# LedCubeControl.net
KiCad netlist of a schematic drawn in EAGLE
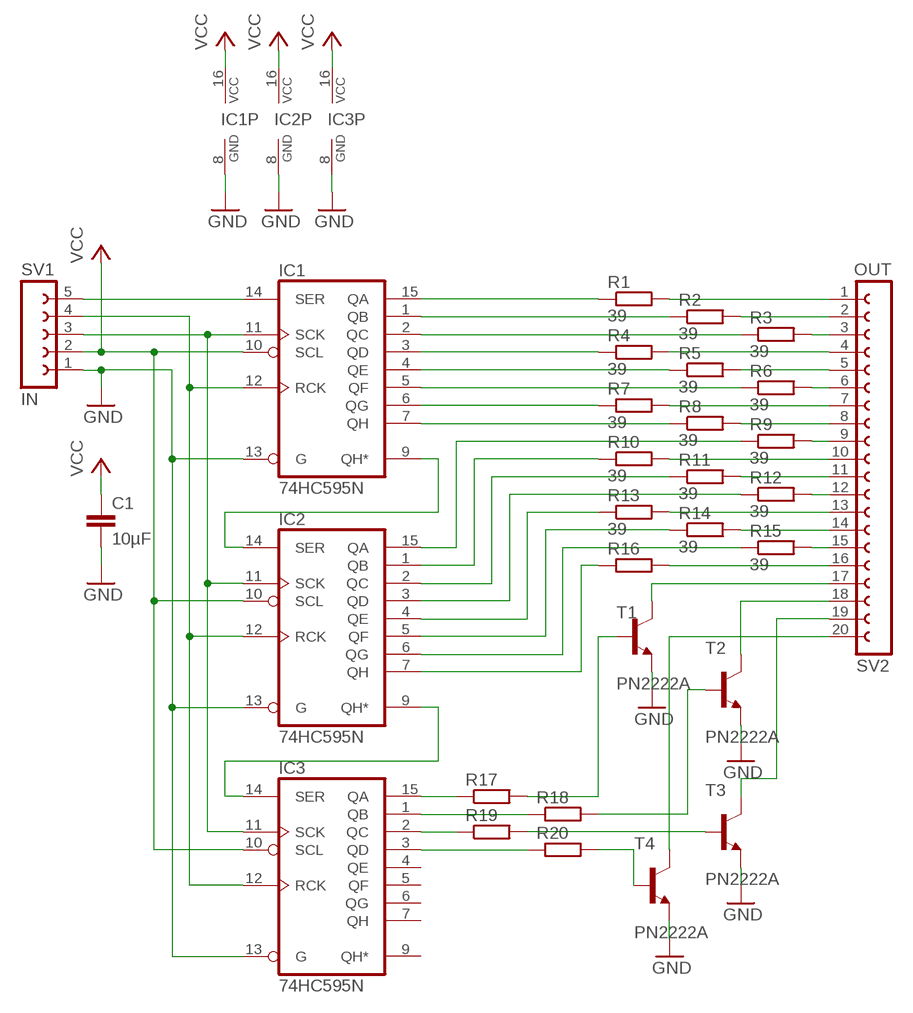
[diagram p0: schematic, sheet 1]

(export (version "E")
  (design (tool "Eeschema 10.0.6"))
  (components
    (comp (ref "C1")
      (value "10µF")
      (footprint "eagle-import:C050-024X044")
      (libsource (lib "eagle-import") (part "C-EU050-024X044"))
    )
    (comp (ref "IC1")
      (value "74HC595N")
      (footprint "eagle-import:DIL16")
      (libsource (lib "eagle-import") (part "74595NHC"))
    )
    (comp (ref "IC2")
      (value "74HC595N")
      (footprint "eagle-import:DIL16")
      (libsource (lib "eagle-import") (part "74595NHC"))
    )
    (comp (ref "IC3")
      (value "74HC595N")
      (footprint "eagle-import:DIL16")
      (libsource (lib "eagle-import") (part "74595NHC"))
    )
    (comp (ref "R1")
      (value "39")
      (footprint "eagle-import:0207_10")
      (libsource (lib "eagle-import") (part "R-EU_0207/10"))
    )
    (comp (ref "R2")
      (value "39")
      (footprint "eagle-import:0207_10")
      (libsource (lib "eagle-import") (part "R-EU_0207/10"))
    )
    (comp (ref "R3")
      (value "39")
      (footprint "eagle-import:0207_10")
      (libsource (lib "eagle-import") (part "R-EU_0207/10"))
    )
    (comp (ref "R4")
      (value "39")
      (footprint "eagle-import:0207_10")
      (libsource (lib "eagle-import") (part "R-EU_0207/10"))
    )
    (comp (ref "R5")
      (value "39")
      (footprint "eagle-import:0207_10")
      (libsource (lib "eagle-import") (part "R-EU_0207/10"))
    )
    (comp (ref "R6")
      (value "39")
      (footprint "eagle-import:0207_10")
      (libsource (lib "eagle-import") (part "R-EU_0207/10"))
    )
    (comp (ref "R7")
      (value "39")
      (footprint "eagle-import:0207_10")
      (libsource (lib "eagle-import") (part "R-EU_0207/10"))
    )
    (comp (ref "R8")
      (value "39")
      (footprint "eagle-import:0207_10")
      (libsource (lib "eagle-import") (part "R-EU_0207/10"))
    )
    (comp (ref "R9")
      (value "39")
      (footprint "eagle-import:0207_10")
      (libsource (lib "eagle-import") (part "R-EU_0207/10"))
    )
    (comp (ref "R10")
      (value "39")
      (footprint "eagle-import:0207_10")
      (libsource (lib "eagle-import") (part "R-EU_0207/10"))
    )
    (comp (ref "R11")
      (value "39")
      (footprint "eagle-import:0207_10")
      (libsource (lib "eagle-import") (part "R-EU_0207/10"))
    )
    (comp (ref "R12")
      (value "39")
      (footprint "eagle-import:0207_10")
      (libsource (lib "eagle-import") (part "R-EU_0207/10"))
    )
    (comp (ref "R13")
      (value "39")
      (footprint "eagle-import:0207_10")
      (libsource (lib "eagle-import") (part "R-EU_0207/10"))
    )
    (comp (ref "R14")
      (value "39")
      (footprint "eagle-import:0207_10")
      (libsource (lib "eagle-import") (part "R-EU_0207/10"))
    )
    (comp (ref "R15")
      (value "39")
      (footprint "eagle-import:0207_10")
      (libsource (lib "eagle-import") (part "R-EU_0207/10"))
    )
    (comp (ref "R16")
      (value "39")
      (footprint "eagle-import:0207_10")
      (libsource (lib "eagle-import") (part "R-EU_0207/10"))
    )
    (comp (ref "R17")
      (value "1k")
      (footprint "eagle-import:0207_10")
      (libsource (lib "eagle-import") (part "R-EU_0207/10"))
    )
    (comp (ref "R18")
      (value "1k")
      (footprint "eagle-import:0207_10")
      (libsource (lib "eagle-import") (part "R-EU_0207/10"))
    )
    (comp (ref "R19")
      (value "1k")
      (footprint "eagle-import:0207_10")
      (libsource (lib "eagle-import") (part "R-EU_0207/10"))
    )
    (comp (ref "R20")
      (value "1k")
      (footprint "eagle-import:0207_10")
      (libsource (lib "eagle-import") (part "R-EU_0207/10"))
    )
    (comp (ref "SV1")
      (value "IN")
      (footprint "eagle-import:FE05-1")
      (libsource (lib "eagle-import") (part "FE05-1"))
    )
    (comp (ref "SV2")
      (value "OUT")
      (footprint "eagle-import:FE20")
      (libsource (lib "eagle-import") (part "FE20-1"))
    )
    (comp (ref "T1")
      (value "PN2222A")
      (footprint "eagle-import:TO92-EBC")
      (libsource (lib "eagle-import") (part "-NPN-TO92-EBCBC317"))
    )
    (comp (ref "T2")
      (value "PN2222A")
      (footprint "eagle-import:TO92-EBC")
      (libsource (lib "eagle-import") (part "-NPN-TO92-EBCBC317"))
    )
    (comp (ref "T3")
      (value "PN2222A")
      (footprint "eagle-import:TO92-EBC")
      (libsource (lib "eagle-import") (part "-NPN-TO92-EBCBC317"))
    )
    (comp (ref "T4")
      (value "PN2222A")
      (footprint "eagle-import:TO92-EBC")
      (libsource (lib "eagle-import") (part "-NPN-TO92-EBCBC317"))
    )
  )
  (nets
    (net (code "1") (name "GND") (class "Default")
      (node (ref "C1") (pin "2") (pinfunction "2_2") (pintype "passive"))
      (node (ref "IC1") (pin "13") (pinfunction "G_13") (pintype "input"))
      (node (ref "IC1") (pin "8") (pinfunction "GND_8") (pintype "power_in"))
      (node (ref "IC2") (pin "13") (pinfunction "G_13") (pintype "input"))
      (node (ref "IC2") (pin "8") (pinfunction "GND_8") (pintype "power_in"))
      (node (ref "IC3") (pin "13") (pinfunction "G_13") (pintype "input"))
      (node (ref "IC3") (pin "8") (pinfunction "GND_8") (pintype "power_in"))
      (node (ref "SV1") (pin "1") (pinfunction "1_1") (pintype "passive"))
      (node (ref "T1") (pin "E") (pinfunction "E_E") (pintype "passive"))
      (node (ref "T2") (pin "E") (pinfunction "E_E") (pintype "passive"))
      (node (ref "T3") (pin "E") (pinfunction "E_E") (pintype "passive"))
      (node (ref "T4") (pin "E") (pinfunction "E_E") (pintype "passive"))
    )
    (net (code "2") (name "Net-(IC1A-QA)") (class "Default")
      (node (ref "IC1") (pin "15") (pinfunction "QA_15") (pintype "tri_state"))
      (node (ref "R1") (pin "1") (pinfunction "1_1") (pintype "passive"))
    )
    (net (code "3") (name "Net-(IC1A-QB)") (class "Default")
      (node (ref "IC1") (pin "1") (pinfunction "QB_1") (pintype "tri_state"))
      (node (ref "R2") (pin "1") (pinfunction "1_1") (pintype "passive"))
    )
    (net (code "4") (name "Net-(IC1A-QC)") (class "Default")
      (node (ref "IC1") (pin "2") (pinfunction "QC_2") (pintype "tri_state"))
      (node (ref "R3") (pin "1") (pinfunction "1_1") (pintype "passive"))
    )
    (net (code "5") (name "Net-(IC1A-QD)") (class "Default")
      (node (ref "IC1") (pin "3") (pinfunction "QD_3") (pintype "tri_state"))
      (node (ref "R4") (pin "1") (pinfunction "1_1") (pintype "passive"))
    )
    (net (code "6") (name "Net-(IC1A-QE)") (class "Default")
      (node (ref "IC1") (pin "4") (pinfunction "QE_4") (pintype "tri_state"))
      (node (ref "R5") (pin "1") (pinfunction "1_1") (pintype "passive"))
    )
    (net (code "7") (name "Net-(IC1A-QF)") (class "Default")
      (node (ref "IC1") (pin "5") (pinfunction "QF_5") (pintype "tri_state"))
      (node (ref "R6") (pin "1") (pinfunction "1_1") (pintype "passive"))
    )
    (net (code "8") (name "Net-(IC1A-QG)") (class "Default")
      (node (ref "IC1") (pin "6") (pinfunction "QG_6") (pintype "tri_state"))
      (node (ref "R7") (pin "1") (pinfunction "1_1") (pintype "passive"))
    )
    (net (code "9") (name "Net-(IC1A-QH)") (class "Default")
      (node (ref "IC1") (pin "7") (pinfunction "QH_7") (pintype "tri_state"))
      (node (ref "R8") (pin "1") (pinfunction "1_1") (pintype "passive"))
    )
    (net (code "10") (name "Net-(IC1A-QH*)") (class "Default")
      (node (ref "IC1") (pin "9") (pinfunction "QH*_9") (pintype "tri_state"))
      (node (ref "IC2") (pin "14") (pinfunction "SER_14") (pintype "input"))
    )
    (net (code "11") (name "Net-(IC1A-RCK)") (class "Default")
      (node (ref "IC1") (pin "12") (pinfunction "RCK_12") (pintype "input"))
      (node (ref "IC2") (pin "12") (pinfunction "RCK_12") (pintype "input"))
      (node (ref "IC3") (pin "12") (pinfunction "RCK_12") (pintype "input"))
      (node (ref "SV1") (pin "4") (pinfunction "4_4") (pintype "passive"))
    )
    (net (code "12") (name "Net-(IC1A-SCK)") (class "Default")
      (node (ref "IC1") (pin "11") (pinfunction "SCK_11") (pintype "input"))
      (node (ref "IC2") (pin "11") (pinfunction "SCK_11") (pintype "input"))
      (node (ref "IC3") (pin "11") (pinfunction "SCK_11") (pintype "input"))
      (node (ref "SV1") (pin "3") (pinfunction "3_3") (pintype "passive"))
    )
    (net (code "13") (name "Net-(IC1A-SER)") (class "Default")
      (node (ref "IC1") (pin "14") (pinfunction "SER_14") (pintype "input"))
      (node (ref "SV1") (pin "5") (pinfunction "5_5") (pintype "passive"))
    )
    (net (code "14") (name "Net-(IC2A-QA)") (class "Default")
      (node (ref "IC2") (pin "15") (pinfunction "QA_15") (pintype "tri_state"))
      (node (ref "R9") (pin "1") (pinfunction "1_1") (pintype "passive"))
    )
    (net (code "15") (name "Net-(IC2A-QB)") (class "Default")
      (node (ref "IC2") (pin "1") (pinfunction "QB_1") (pintype "tri_state"))
      (node (ref "R10") (pin "1") (pinfunction "1_1") (pintype "passive"))
    )
    (net (code "16") (name "Net-(IC2A-QC)") (class "Default")
      (node (ref "IC2") (pin "2") (pinfunction "QC_2") (pintype "tri_state"))
      (node (ref "R11") (pin "1") (pinfunction "1_1") (pintype "passive"))
    )
    (net (code "17") (name "Net-(IC2A-QD)") (class "Default")
      (node (ref "IC2") (pin "3") (pinfunction "QD_3") (pintype "tri_state"))
      (node (ref "R12") (pin "1") (pinfunction "1_1") (pintype "passive"))
    )
    (net (code "18") (name "Net-(IC2A-QE)") (class "Default")
      (node (ref "IC2") (pin "4") (pinfunction "QE_4") (pintype "tri_state"))
      (node (ref "R13") (pin "1") (pinfunction "1_1") (pintype "passive"))
    )
    (net (code "19") (name "Net-(IC2A-QF)") (class "Default")
      (node (ref "IC2") (pin "5") (pinfunction "QF_5") (pintype "tri_state"))
      (node (ref "R14") (pin "1") (pinfunction "1_1") (pintype "passive"))
    )
    (net (code "20") (name "Net-(IC2A-QG)") (class "Default")
      (node (ref "IC2") (pin "6") (pinfunction "QG_6") (pintype "tri_state"))
      (node (ref "R15") (pin "1") (pinfunction "1_1") (pintype "passive"))
    )
    (net (code "21") (name "Net-(IC2A-QH)") (class "Default")
      (node (ref "IC2") (pin "7") (pinfunction "QH_7") (pintype "tri_state"))
      (node (ref "R16") (pin "1") (pinfunction "1_1") (pintype "passive"))
    )
    (net (code "22") (name "Net-(IC2A-QH*)") (class "Default")
      (node (ref "IC2") (pin "9") (pinfunction "QH*_9") (pintype "tri_state"))
      (node (ref "IC3") (pin "14") (pinfunction "SER_14") (pintype "input"))
    )
    (net (code "23") (name "Net-(IC3A-QA)") (class "Default")
      (node (ref "IC3") (pin "15") (pinfunction "QA_15") (pintype "tri_state"))
      (node (ref "R17") (pin "1") (pinfunction "1_1") (pintype "passive"))
    )
    (net (code "24") (name "Net-(IC3A-QB)") (class "Default")
      (node (ref "IC3") (pin "1") (pinfunction "QB_1") (pintype "tri_state"))
      (node (ref "R18") (pin "1") (pinfunction "1_1") (pintype "passive"))
    )
    (net (code "25") (name "Net-(IC3A-QC)") (class "Default")
      (node (ref "IC3") (pin "2") (pinfunction "QC_2") (pintype "tri_state"))
      (node (ref "R19") (pin "1") (pinfunction "1_1") (pintype "passive"))
    )
    (net (code "26") (name "Net-(IC3A-QD)") (class "Default")
      (node (ref "IC3") (pin "3") (pinfunction "QD_3") (pintype "tri_state"))
      (node (ref "R20") (pin "1") (pinfunction "1_1") (pintype "passive"))
    )
    (net (code "27") (name "Net-(R1-Pad2)") (class "Default")
      (node (ref "R1") (pin "2") (pinfunction "2_2") (pintype "passive"))
      (node (ref "SV2") (pin "1") (pinfunction "1_1") (pintype "passive"))
    )
    (net (code "28") (name "Net-(R2-Pad2)") (class "Default")
      (node (ref "R2") (pin "2") (pinfunction "2_2") (pintype "passive"))
      (node (ref "SV2") (pin "2") (pinfunction "2_2") (pintype "passive"))
    )
    (net (code "29") (name "Net-(R3-Pad2)") (class "Default")
      (node (ref "R3") (pin "2") (pinfunction "2_2") (pintype "passive"))
      (node (ref "SV2") (pin "3") (pinfunction "3_3") (pintype "passive"))
    )
    (net (code "30") (name "Net-(R4-Pad2)") (class "Default")
      (node (ref "R4") (pin "2") (pinfunction "2_2") (pintype "passive"))
      (node (ref "SV2") (pin "4") (pinfunction "4_4") (pintype "passive"))
    )
    (net (code "31") (name "Net-(R5-Pad2)") (class "Default")
      (node (ref "R5") (pin "2") (pinfunction "2_2") (pintype "passive"))
      (node (ref "SV2") (pin "5") (pinfunction "5_5") (pintype "passive"))
    )
    (net (code "32") (name "Net-(R6-Pad2)") (class "Default")
      (node (ref "R6") (pin "2") (pinfunction "2_2") (pintype "passive"))
      (node (ref "SV2") (pin "6") (pinfunction "6_6") (pintype "passive"))
    )
    (net (code "33") (name "Net-(R7-Pad2)") (class "Default")
      (node (ref "R7") (pin "2") (pinfunction "2_2") (pintype "passive"))
      (node (ref "SV2") (pin "7") (pinfunction "7_7") (pintype "passive"))
    )
    (net (code "34") (name "Net-(R8-Pad2)") (class "Default")
      (node (ref "R8") (pin "2") (pinfunction "2_2") (pintype "passive"))
      (node (ref "SV2") (pin "8") (pinfunction "8_8") (pintype "passive"))
    )
    (net (code "35") (name "Net-(R9-Pad2)") (class "Default")
      (node (ref "R9") (pin "2") (pinfunction "2_2") (pintype "passive"))
      (node (ref "SV2") (pin "9") (pinfunction "9_9") (pintype "passive"))
    )
    (net (code "36") (name "Net-(R10-Pad2)") (class "Default")
      (node (ref "R10") (pin "2") (pinfunction "2_2") (pintype "passive"))
      (node (ref "SV2") (pin "10") (pinfunction "10_10") (pintype "passive"))
    )
    (net (code "37") (name "Net-(R11-Pad2)") (class "Default")
      (node (ref "R11") (pin "2") (pinfunction "2_2") (pintype "passive"))
      (node (ref "SV2") (pin "11") (pinfunction "11_11") (pintype "passive"))
    )
    (net (code "38") (name "Net-(R12-Pad2)") (class "Default")
      (node (ref "R12") (pin "2") (pinfunction "2_2") (pintype "passive"))
      (node (ref "SV2") (pin "12") (pinfunction "12_12") (pintype "passive"))
    )
    (net (code "39") (name "Net-(R13-Pad2)") (class "Default")
      (node (ref "R13") (pin "2") (pinfunction "2_2") (pintype "passive"))
      (node (ref "SV2") (pin "13") (pinfunction "13_13") (pintype "passive"))
    )
    (net (code "40") (name "Net-(R14-Pad2)") (class "Default")
      (node (ref "R14") (pin "2") (pinfunction "2_2") (pintype "passive"))
      (node (ref "SV2") (pin "14") (pinfunction "14_14") (pintype "passive"))
    )
    (net (code "41") (name "Net-(R15-Pad2)") (class "Default")
      (node (ref "R15") (pin "2") (pinfunction "2_2") (pintype "passive"))
      (node (ref "SV2") (pin "15") (pinfunction "15_15") (pintype "passive"))
    )
    (net (code "42") (name "Net-(R16-Pad2)") (class "Default")
      (node (ref "R16") (pin "2") (pinfunction "2_2") (pintype "passive"))
      (node (ref "SV2") (pin "16") (pinfunction "16_16") (pintype "passive"))
    )
    (net (code "43") (name "Net-(R17-Pad2)") (class "Default")
      (node (ref "R17") (pin "2") (pinfunction "2_2") (pintype "passive"))
      (node (ref "T1") (pin "B") (pinfunction "B_B") (pintype "passive"))
    )
    (net (code "44") (name "Net-(R18-Pad2)") (class "Default")
      (node (ref "R18") (pin "2") (pinfunction "2_2") (pintype "passive"))
      (node (ref "T2") (pin "B") (pinfunction "B_B") (pintype "passive"))
    )
    (net (code "45") (name "Net-(R19-Pad2)") (class "Default")
      (node (ref "R19") (pin "2") (pinfunction "2_2") (pintype "passive"))
      (node (ref "T3") (pin "B") (pinfunction "B_B") (pintype "passive"))
    )
    (net (code "46") (name "Net-(R20-Pad2)") (class "Default")
      (node (ref "R20") (pin "2") (pinfunction "2_2") (pintype "passive"))
      (node (ref "T4") (pin "B") (pinfunction "B_B") (pintype "passive"))
    )
    (net (code "47") (name "Net-(SV2-Pad17)") (class "Default")
      (node (ref "SV2") (pin "17") (pinfunction "17_17") (pintype "passive"))
      (node (ref "T1") (pin "C") (pinfunction "C_C") (pintype "passive"))
    )
    (net (code "48") (name "Net-(SV2-Pad18)") (class "Default")
      (node (ref "SV2") (pin "18") (pinfunction "18_18") (pintype "passive"))
      (node (ref "T2") (pin "C") (pinfunction "C_C") (pintype "passive"))
    )
    (net (code "49") (name "Net-(SV2-Pad19)") (class "Default")
      (node (ref "SV2") (pin "19") (pinfunction "19_19") (pintype "passive"))
      (node (ref "T3") (pin "C") (pinfunction "C_C") (pintype "passive"))
    )
    (net (code "50") (name "Net-(SV2-Pad20)") (class "Default")
      (node (ref "SV2") (pin "20") (pinfunction "20_20") (pintype "passive"))
      (node (ref "T4") (pin "C") (pinfunction "C_C") (pintype "passive"))
    )
    (net (code "51") (name "VCC") (class "Default")
      (node (ref "C1") (pin "1") (pinfunction "1_1") (pintype "passive"))
      (node (ref "IC1") (pin "10") (pinfunction "SCL_10") (pintype "input"))
      (node (ref "IC1") (pin "16") (pinfunction "VCC_16") (pintype "power_in"))
      (node (ref "IC2") (pin "10") (pinfunction "SCL_10") (pintype "input"))
      (node (ref "IC2") (pin "16") (pinfunction "VCC_16") (pintype "power_in"))
      (node (ref "IC3") (pin "10") (pinfunction "SCL_10") (pintype "input"))
      (node (ref "IC3") (pin "16") (pinfunction "VCC_16") (pintype "power_in"))
      (node (ref "SV1") (pin "2") (pinfunction "2_2") (pintype "passive"))
    )
    (net (code "52") (name "unconnected-(IC3A-QE-Pad4)") (class "Default")
      (node (ref "IC3") (pin "4") (pinfunction "QE_4") (pintype "tri_state"))
    )
    (net (code "53") (name "unconnected-(IC3A-QF-Pad5)") (class "Default")
      (node (ref "IC3") (pin "5") (pinfunction "QF_5") (pintype "tri_state"))
    )
    (net (code "54") (name "unconnected-(IC3A-QG-Pad6)") (class "Default")
      (node (ref "IC3") (pin "6") (pinfunction "QG_6") (pintype "tri_state"))
    )
    (net (code "55") (name "unconnected-(IC3A-QH*-Pad9)") (class "Default")
      (node (ref "IC3") (pin "9") (pinfunction "QH*_9") (pintype "tri_state"))
    )
    (net (code "56") (name "unconnected-(IC3A-QH-Pad7)") (class "Default")
      (node (ref "IC3") (pin "7") (pinfunction "QH_7") (pintype "tri_state"))
    )
  )
)
